# Connections.net
KiCad netlist of a schematic drawn in Altium Designer
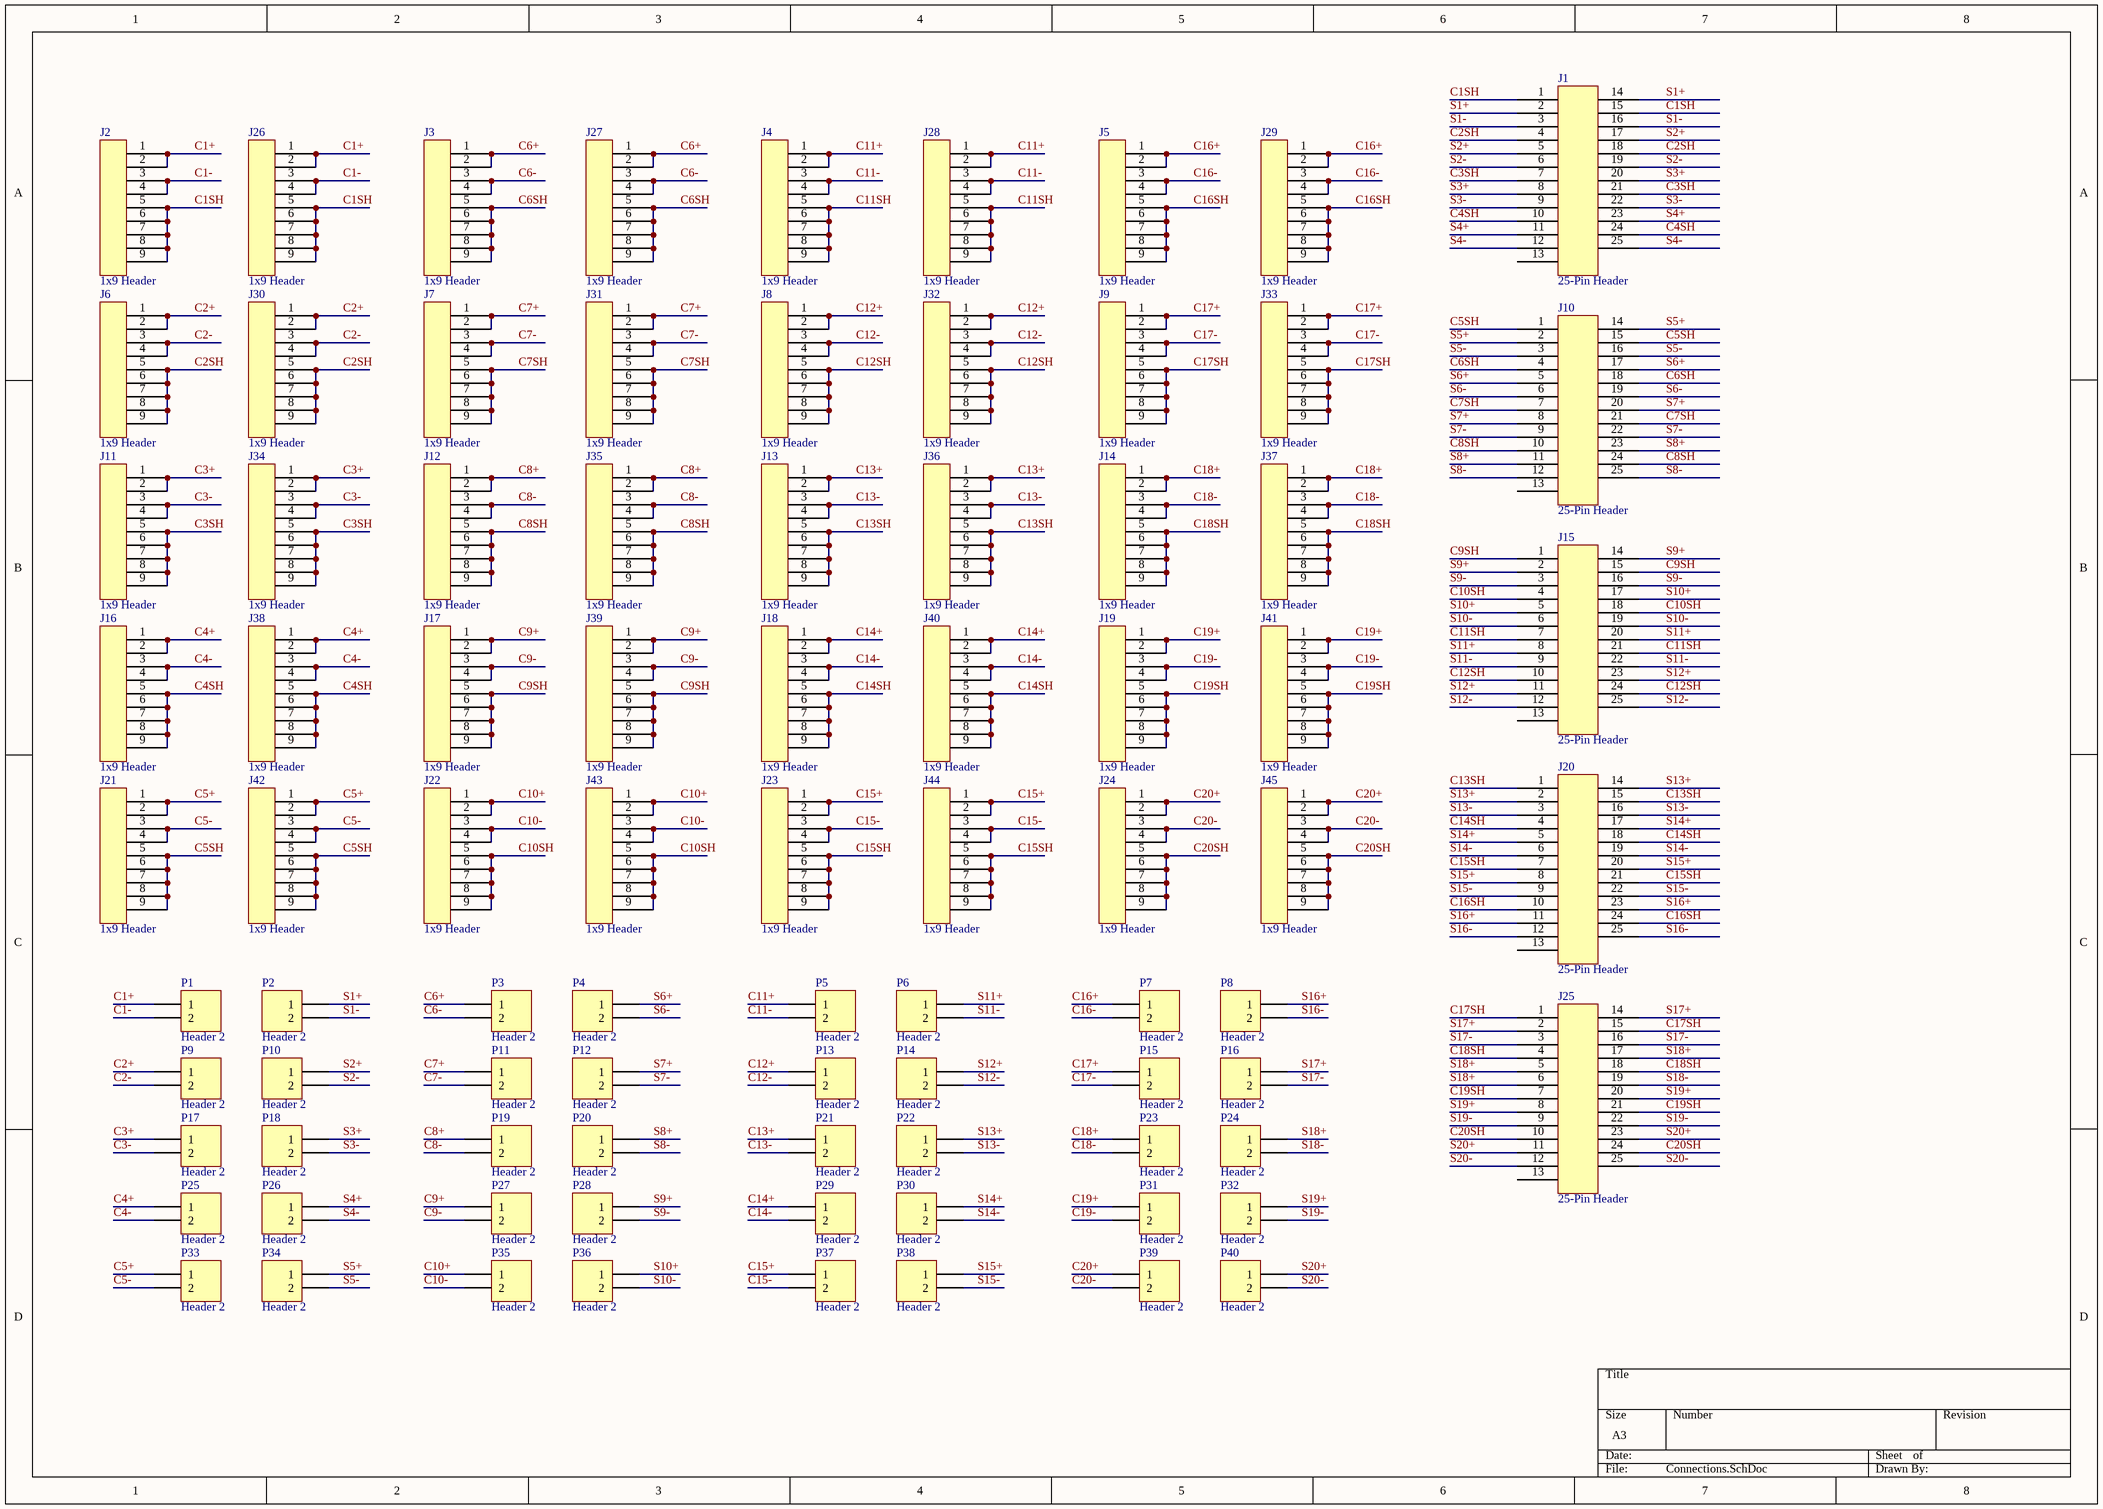
[diagram p0: Connections.SchDoc]

(export (version "E")
  (design (tool "Eeschema 10.0.6"))
  (components
    (comp (ref "J1")
      (value "25-Pin Header")
      (footprint "25-DSub-Rightangle-Female")
      (description "25-Pin Header DSub")
      (libsource (lib "Schematic_Components") (part "25-Pin Header"))
    )
    (comp (ref "J2")
      (value "1x9 Header")
      (footprint "D-SUB-9PIN-TE")
      (libsource (lib "Schematic_Components") (part "1x9 Header"))
    )
    (comp (ref "J3")
      (value "1x9 Header")
      (footprint "D-SUB-9PIN-TE")
      (libsource (lib "Schematic_Components") (part "1x9 Header"))
    )
    (comp (ref "J4")
      (value "1x9 Header")
      (footprint "D-SUB-9PIN-TE")
      (libsource (lib "Schematic_Components") (part "1x9 Header"))
    )
    (comp (ref "J5")
      (value "1x9 Header")
      (footprint "D-SUB-9PIN-TE")
      (libsource (lib "Schematic_Components") (part "1x9 Header"))
    )
    (comp (ref "J6")
      (value "1x9 Header")
      (footprint "D-SUB-9PIN-TE")
      (libsource (lib "Schematic_Components") (part "1x9 Header"))
    )
    (comp (ref "J7")
      (value "1x9 Header")
      (footprint "D-SUB-9PIN-TE")
      (libsource (lib "Schematic_Components") (part "1x9 Header"))
    )
    (comp (ref "J8")
      (value "1x9 Header")
      (footprint "D-SUB-9PIN-TE")
      (libsource (lib "Schematic_Components") (part "1x9 Header"))
    )
    (comp (ref "J9")
      (value "1x9 Header")
      (footprint "D-SUB-9PIN-TE")
      (libsource (lib "Schematic_Components") (part "1x9 Header"))
    )
    (comp (ref "J10")
      (value "25-Pin Header")
      (footprint "25-DSub-Rightangle-Female")
      (description "25-Pin Header DSub")
      (libsource (lib "Schematic_Components") (part "25-Pin Header"))
    )
    (comp (ref "J11")
      (value "1x9 Header")
      (footprint "D-SUB-9PIN-TE")
      (libsource (lib "Schematic_Components") (part "1x9 Header"))
    )
    (comp (ref "J12")
      (value "1x9 Header")
      (footprint "D-SUB-9PIN-TE")
      (libsource (lib "Schematic_Components") (part "1x9 Header"))
    )
    (comp (ref "J13")
      (value "1x9 Header")
      (footprint "D-SUB-9PIN-TE")
      (libsource (lib "Schematic_Components") (part "1x9 Header"))
    )
    (comp (ref "J14")
      (value "1x9 Header")
      (footprint "D-SUB-9PIN-TE")
      (libsource (lib "Schematic_Components") (part "1x9 Header"))
    )
    (comp (ref "J15")
      (value "25-Pin Header")
      (footprint "25-DSub-Rightangle-Female")
      (description "25-Pin Header DSub")
      (libsource (lib "Schematic_Components") (part "25-Pin Header"))
    )
    (comp (ref "J16")
      (value "1x9 Header")
      (footprint "D-SUB-9PIN-TE")
      (libsource (lib "Schematic_Components") (part "1x9 Header"))
    )
    (comp (ref "J17")
      (value "1x9 Header")
      (footprint "D-SUB-9PIN-TE")
      (libsource (lib "Schematic_Components") (part "1x9 Header"))
    )
    (comp (ref "J18")
      (value "1x9 Header")
      (footprint "D-SUB-9PIN-TE")
      (libsource (lib "Schematic_Components") (part "1x9 Header"))
    )
    (comp (ref "J19")
      (value "1x9 Header")
      (footprint "D-SUB-9PIN-TE")
      (libsource (lib "Schematic_Components") (part "1x9 Header"))
    )
    (comp (ref "J20")
      (value "25-Pin Header")
      (footprint "25-DSub-Rightangle-Female")
      (description "25-Pin Header DSub")
      (libsource (lib "Schematic_Components") (part "25-Pin Header"))
    )
    (comp (ref "J21")
      (value "1x9 Header")
      (footprint "D-SUB-9PIN-TE")
      (libsource (lib "Schematic_Components") (part "1x9 Header"))
    )
    (comp (ref "J22")
      (value "1x9 Header")
      (footprint "D-SUB-9PIN-TE")
      (libsource (lib "Schematic_Components") (part "1x9 Header"))
    )
    (comp (ref "J23")
      (value "1x9 Header")
      (footprint "D-SUB-9PIN-TE")
      (libsource (lib "Schematic_Components") (part "1x9 Header"))
    )
    (comp (ref "J24")
      (value "1x9 Header")
      (footprint "D-SUB-9PIN-TE")
      (libsource (lib "Schematic_Components") (part "1x9 Header"))
    )
    (comp (ref "J25")
      (value "25-Pin Header")
      (footprint "25-DSub-Rightangle-Female")
      (description "25-Pin Header DSub")
      (libsource (lib "Schematic_Components") (part "25-Pin Header"))
    )
    (comp (ref "J26")
      (value "1x9 Header")
      (footprint "D-SUB-9PIN-TE")
      (libsource (lib "Schematic_Components") (part "1x9 Header"))
    )
    (comp (ref "J27")
      (value "1x9 Header")
      (footprint "D-SUB-9PIN-TE")
      (libsource (lib "Schematic_Components") (part "1x9 Header"))
    )
    (comp (ref "J28")
      (value "1x9 Header")
      (footprint "D-SUB-9PIN-TE")
      (libsource (lib "Schematic_Components") (part "1x9 Header"))
    )
    (comp (ref "J29")
      (value "1x9 Header")
      (footprint "D-SUB-9PIN-TE")
      (libsource (lib "Schematic_Components") (part "1x9 Header"))
    )
    (comp (ref "J30")
      (value "1x9 Header")
      (footprint "D-SUB-9PIN-TE")
      (libsource (lib "Schematic_Components") (part "1x9 Header"))
    )
    (comp (ref "J31")
      (value "1x9 Header")
      (footprint "D-SUB-9PIN-TE")
      (libsource (lib "Schematic_Components") (part "1x9 Header"))
    )
    (comp (ref "J32")
      (value "1x9 Header")
      (footprint "D-SUB-9PIN-TE")
      (libsource (lib "Schematic_Components") (part "1x9 Header"))
    )
    (comp (ref "J33")
      (value "1x9 Header")
      (footprint "D-SUB-9PIN-TE")
      (libsource (lib "Schematic_Components") (part "1x9 Header"))
    )
    (comp (ref "J34")
      (value "1x9 Header")
      (footprint "D-SUB-9PIN-TE")
      (libsource (lib "Schematic_Components") (part "1x9 Header"))
    )
    (comp (ref "J35")
      (value "1x9 Header")
      (footprint "D-SUB-9PIN-TE")
      (libsource (lib "Schematic_Components") (part "1x9 Header"))
    )
    (comp (ref "J36")
      (value "1x9 Header")
      (footprint "D-SUB-9PIN-TE")
      (libsource (lib "Schematic_Components") (part "1x9 Header"))
    )
    (comp (ref "J37")
      (value "1x9 Header")
      (footprint "D-SUB-9PIN-TE")
      (libsource (lib "Schematic_Components") (part "1x9 Header"))
    )
    (comp (ref "J38")
      (value "1x9 Header")
      (footprint "D-SUB-9PIN-TE")
      (libsource (lib "Schematic_Components") (part "1x9 Header"))
    )
    (comp (ref "J39")
      (value "1x9 Header")
      (footprint "D-SUB-9PIN-TE")
      (libsource (lib "Schematic_Components") (part "1x9 Header"))
    )
    (comp (ref "J40")
      (value "1x9 Header")
      (footprint "D-SUB-9PIN-TE")
      (libsource (lib "Schematic_Components") (part "1x9 Header"))
    )
    (comp (ref "J41")
      (value "1x9 Header")
      (footprint "D-SUB-9PIN-TE")
      (libsource (lib "Schematic_Components") (part "1x9 Header"))
    )
    (comp (ref "J42")
      (value "1x9 Header")
      (footprint "D-SUB-9PIN-TE")
      (libsource (lib "Schematic_Components") (part "1x9 Header"))
    )
    (comp (ref "J43")
      (value "1x9 Header")
      (footprint "D-SUB-9PIN-TE")
      (libsource (lib "Schematic_Components") (part "1x9 Header"))
    )
    (comp (ref "J44")
      (value "1x9 Header")
      (footprint "D-SUB-9PIN-TE")
      (libsource (lib "Schematic_Components") (part "1x9 Header"))
    )
    (comp (ref "J45")
      (value "1x9 Header")
      (footprint "D-SUB-9PIN-TE")
      (libsource (lib "Schematic_Components") (part "1x9 Header"))
    )
    (comp (ref "P1")
      (value "Header 2")
      (footprint "HDR1X2")
      (description "Header, 2-Pin")
      (fields (field (name "PUBLISHER") "Altium Limited"))
      (libsource (lib "Miscellaneous Connectors") (part "Header 2"))
    )
    (comp (ref "P2")
      (value "Header 2")
      (footprint "HDR1X2")
      (description "Header, 2-Pin")
      (fields (field (name "PUBLISHER") "Altium Limited"))
      (libsource (lib "") (part "Header 2_1"))
    )
    (comp (ref "P3")
      (value "Header 2")
      (footprint "HDR1X2")
      (description "Header, 2-Pin")
      (fields (field (name "PUBLISHER") "Altium Limited"))
      (libsource (lib "Miscellaneous Connectors") (part "Header 2"))
    )
    (comp (ref "P4")
      (value "Header 2")
      (footprint "HDR1X2")
      (description "Header, 2-Pin")
      (fields (field (name "PUBLISHER") "Altium Limited"))
      (libsource (lib "") (part "Header 2_1"))
    )
    (comp (ref "P5")
      (value "Header 2")
      (footprint "HDR1X2")
      (description "Header, 2-Pin")
      (fields (field (name "PUBLISHER") "Altium Limited"))
      (libsource (lib "Miscellaneous Connectors") (part "Header 2"))
    )
    (comp (ref "P6")
      (value "Header 2")
      (footprint "HDR1X2")
      (description "Header, 2-Pin")
      (fields (field (name "PUBLISHER") "Altium Limited"))
      (libsource (lib "") (part "Header 2_1"))
    )
    (comp (ref "P7")
      (value "Header 2")
      (footprint "HDR1X2")
      (description "Header, 2-Pin")
      (fields (field (name "PUBLISHER") "Altium Limited"))
      (libsource (lib "Miscellaneous Connectors") (part "Header 2"))
    )
    (comp (ref "P8")
      (value "Header 2")
      (footprint "HDR1X2")
      (description "Header, 2-Pin")
      (fields (field (name "PUBLISHER") "Altium Limited"))
      (libsource (lib "") (part "Header 2_1"))
    )
    (comp (ref "P9")
      (value "Header 2")
      (footprint "HDR1X2")
      (description "Header, 2-Pin")
      (fields (field (name "PUBLISHER") "Altium Limited"))
      (libsource (lib "Miscellaneous Connectors") (part "Header 2"))
    )
    (comp (ref "P10")
      (value "Header 2")
      (footprint "HDR1X2")
      (description "Header, 2-Pin")
      (fields (field (name "PUBLISHER") "Altium Limited"))
      (libsource (lib "") (part "Header 2_1"))
    )
    (comp (ref "P11")
      (value "Header 2")
      (footprint "HDR1X2")
      (description "Header, 2-Pin")
      (fields (field (name "PUBLISHER") "Altium Limited"))
      (libsource (lib "Miscellaneous Connectors") (part "Header 2"))
    )
    (comp (ref "P12")
      (value "Header 2")
      (footprint "HDR1X2")
      (description "Header, 2-Pin")
      (fields (field (name "PUBLISHER") "Altium Limited"))
      (libsource (lib "") (part "Header 2_1"))
    )
    (comp (ref "P13")
      (value "Header 2")
      (footprint "HDR1X2")
      (description "Header, 2-Pin")
      (fields (field (name "PUBLISHER") "Altium Limited"))
      (libsource (lib "Miscellaneous Connectors") (part "Header 2"))
    )
    (comp (ref "P14")
      (value "Header 2")
      (footprint "HDR1X2")
      (description "Header, 2-Pin")
      (fields (field (name "PUBLISHER") "Altium Limited"))
      (libsource (lib "") (part "Header 2_1"))
    )
    (comp (ref "P15")
      (value "Header 2")
      (footprint "HDR1X2")
      (description "Header, 2-Pin")
      (fields (field (name "PUBLISHER") "Altium Limited"))
      (libsource (lib "Miscellaneous Connectors") (part "Header 2"))
    )
    (comp (ref "P16")
      (value "Header 2")
      (footprint "HDR1X2")
      (description "Header, 2-Pin")
      (fields (field (name "PUBLISHER") "Altium Limited"))
      (libsource (lib "") (part "Header 2_1"))
    )
    (comp (ref "P17")
      (value "Header 2")
      (footprint "HDR1X2")
      (description "Header, 2-Pin")
      (fields (field (name "PUBLISHER") "Altium Limited"))
      (libsource (lib "Miscellaneous Connectors") (part "Header 2"))
    )
    (comp (ref "P18")
      (value "Header 2")
      (footprint "HDR1X2")
      (description "Header, 2-Pin")
      (fields (field (name "PUBLISHER") "Altium Limited"))
      (libsource (lib "") (part "Header 2_1"))
    )
    (comp (ref "P19")
      (value "Header 2")
      (footprint "HDR1X2")
      (description "Header, 2-Pin")
      (fields (field (name "PUBLISHER") "Altium Limited"))
      (libsource (lib "Miscellaneous Connectors") (part "Header 2"))
    )
    (comp (ref "P20")
      (value "Header 2")
      (footprint "HDR1X2")
      (description "Header, 2-Pin")
      (fields (field (name "PUBLISHER") "Altium Limited"))
      (libsource (lib "") (part "Header 2_1"))
    )
    (comp (ref "P21")
      (value "Header 2")
      (footprint "HDR1X2")
      (description "Header, 2-Pin")
      (fields (field (name "PUBLISHER") "Altium Limited"))
      (libsource (lib "Miscellaneous Connectors") (part "Header 2"))
    )
    (comp (ref "P22")
      (value "Header 2")
      (footprint "HDR1X2")
      (description "Header, 2-Pin")
      (fields (field (name "PUBLISHER") "Altium Limited"))
      (libsource (lib "") (part "Header 2_1"))
    )
    (comp (ref "P23")
      (value "Header 2")
      (footprint "HDR1X2")
      (description "Header, 2-Pin")
      (fields (field (name "PUBLISHER") "Altium Limited"))
      (libsource (lib "Miscellaneous Connectors") (part "Header 2"))
    )
    (comp (ref "P24")
      (value "Header 2")
      (footprint "HDR1X2")
      (description "Header, 2-Pin")
      (fields (field (name "PUBLISHER") "Altium Limited"))
      (libsource (lib "") (part "Header 2_1"))
    )
    (comp (ref "P25")
      (value "Header 2")
      (footprint "HDR1X2")
      (description "Header, 2-Pin")
      (fields (field (name "PUBLISHER") "Altium Limited"))
      (libsource (lib "Miscellaneous Connectors") (part "Header 2"))
    )
    (comp (ref "P26")
      (value "Header 2")
      (footprint "HDR1X2")
      (description "Header, 2-Pin")
      (fields (field (name "PUBLISHER") "Altium Limited"))
      (libsource (lib "") (part "Header 2_1"))
    )
    (comp (ref "P27")
      (value "Header 2")
      (footprint "HDR1X2")
      (description "Header, 2-Pin")
      (fields (field (name "PUBLISHER") "Altium Limited"))
      (libsource (lib "Miscellaneous Connectors") (part "Header 2"))
    )
    (comp (ref "P28")
      (value "Header 2")
      (footprint "HDR1X2")
      (description "Header, 2-Pin")
      (fields (field (name "PUBLISHER") "Altium Limited"))
      (libsource (lib "") (part "Header 2_1"))
    )
    (comp (ref "P29")
      (value "Header 2")
      (footprint "HDR1X2")
      (description "Header, 2-Pin")
      (fields (field (name "PUBLISHER") "Altium Limited"))
      (libsource (lib "Miscellaneous Connectors") (part "Header 2"))
    )
    (comp (ref "P30")
      (value "Header 2")
      (footprint "HDR1X2")
      (description "Header, 2-Pin")
      (fields (field (name "PUBLISHER") "Altium Limited"))
      (libsource (lib "") (part "Header 2_1"))
    )
    (comp (ref "P31")
      (value "Header 2")
      (footprint "HDR1X2")
      (description "Header, 2-Pin")
      (fields (field (name "PUBLISHER") "Altium Limited"))
      (libsource (lib "Miscellaneous Connectors") (part "Header 2"))
    )
    (comp (ref "P32")
      (value "Header 2")
      (footprint "HDR1X2")
      (description "Header, 2-Pin")
      (fields (field (name "PUBLISHER") "Altium Limited"))
      (libsource (lib "") (part "Header 2_1"))
    )
    (comp (ref "P33")
      (value "Header 2")
      (footprint "HDR1X2")
      (description "Header, 2-Pin")
      (fields (field (name "PUBLISHER") "Altium Limited"))
      (libsource (lib "Miscellaneous Connectors") (part "Header 2"))
    )
    (comp (ref "P34")
      (value "Header 2")
      (footprint "HDR1X2")
      (description "Header, 2-Pin")
      (fields (field (name "PUBLISHER") "Altium Limited"))
      (libsource (lib "") (part "Header 2_1"))
    )
    (comp (ref "P35")
      (value "Header 2")
      (footprint "HDR1X2")
      (description "Header, 2-Pin")
      (fields (field (name "PUBLISHER") "Altium Limited"))
      (libsource (lib "Miscellaneous Connectors") (part "Header 2"))
    )
    (comp (ref "P36")
      (value "Header 2")
      (footprint "HDR1X2")
      (description "Header, 2-Pin")
      (fields (field (name "PUBLISHER") "Altium Limited"))
      (libsource (lib "") (part "Header 2_1"))
    )
    (comp (ref "P37")
      (value "Header 2")
      (footprint "HDR1X2")
      (description "Header, 2-Pin")
      (fields (field (name "PUBLISHER") "Altium Limited"))
      (libsource (lib "Miscellaneous Connectors") (part "Header 2"))
    )
    (comp (ref "P38")
      (value "Header 2")
      (footprint "HDR1X2")
      (description "Header, 2-Pin")
      (fields (field (name "PUBLISHER") "Altium Limited"))
      (libsource (lib "") (part "Header 2_1"))
    )
    (comp (ref "P39")
      (value "Header 2")
      (footprint "HDR1X2")
      (description "Header, 2-Pin")
      (fields (field (name "PUBLISHER") "Altium Limited"))
      (libsource (lib "Miscellaneous Connectors") (part "Header 2"))
    )
    (comp (ref "P40")
      (value "Header 2")
      (footprint "HDR1X2")
      (description "Header, 2-Pin")
      (fields (field (name "PUBLISHER") "Altium Limited"))
      (libsource (lib "") (part "Header 2_1"))
    )
  )
  (nets
    (net (code "1") (name "/C1+") (class "Default")
      (node (ref "J2") (pin "1") (pintype "passive"))
      (node (ref "J2") (pin "2") (pintype "passive"))
      (node (ref "J26") (pin "1") (pintype "passive"))
      (node (ref "J26") (pin "2") (pintype "passive"))
      (node (ref "P1") (pin "1") (pinfunction "1_1") (pintype "passive"))
    )
    (net (code "2") (name "/C1-") (class "Default")
      (node (ref "J2") (pin "3") (pintype "passive"))
      (node (ref "J2") (pin "4") (pintype "passive"))
      (node (ref "J26") (pin "3") (pintype "passive"))
      (node (ref "J26") (pin "4") (pintype "passive"))
      (node (ref "P1") (pin "2") (pinfunction "2_2") (pintype "passive"))
    )
    (net (code "3") (name "/C1SH") (class "Default")
      (node (ref "J1") (pin "1") (pintype "passive"))
      (node (ref "J1") (pin "15") (pintype "passive"))
      (node (ref "J2") (pin "5") (pintype "passive"))
      (node (ref "J2") (pin "6") (pintype "passive"))
      (node (ref "J2") (pin "7") (pintype "passive"))
      (node (ref "J2") (pin "8") (pintype "passive"))
      (node (ref "J2") (pin "9") (pintype "passive"))
      (node (ref "J26") (pin "5") (pintype "passive"))
      (node (ref "J26") (pin "6") (pintype "passive"))
      (node (ref "J26") (pin "7") (pintype "passive"))
      (node (ref "J26") (pin "8") (pintype "passive"))
      (node (ref "J26") (pin "9") (pintype "passive"))
    )
    (net (code "4") (name "/C2+") (class "Default")
      (node (ref "J30") (pin "1") (pintype "passive"))
      (node (ref "J30") (pin "2") (pintype "passive"))
      (node (ref "J6") (pin "1") (pintype "passive"))
      (node (ref "J6") (pin "2") (pintype "passive"))
      (node (ref "P9") (pin "1") (pinfunction "1_1") (pintype "passive"))
    )
    (net (code "5") (name "/C2-") (class "Default")
      (node (ref "J30") (pin "3") (pintype "passive"))
      (node (ref "J30") (pin "4") (pintype "passive"))
      (node (ref "J6") (pin "3") (pintype "passive"))
      (node (ref "J6") (pin "4") (pintype "passive"))
      (node (ref "P9") (pin "2") (pinfunction "2_2") (pintype "passive"))
    )
    (net (code "6") (name "/C2SH") (class "Default")
      (node (ref "J1") (pin "18") (pintype "passive"))
      (node (ref "J1") (pin "4") (pintype "passive"))
      (node (ref "J30") (pin "5") (pintype "passive"))
      (node (ref "J30") (pin "6") (pintype "passive"))
      (node (ref "J30") (pin "7") (pintype "passive"))
      (node (ref "J30") (pin "8") (pintype "passive"))
      (node (ref "J30") (pin "9") (pintype "passive"))
      (node (ref "J6") (pin "5") (pintype "passive"))
      (node (ref "J6") (pin "6") (pintype "passive"))
      (node (ref "J6") (pin "7") (pintype "passive"))
      (node (ref "J6") (pin "8") (pintype "passive"))
      (node (ref "J6") (pin "9") (pintype "passive"))
    )
    (net (code "7") (name "/C3+") (class "Default")
      (node (ref "J11") (pin "1") (pintype "passive"))
      (node (ref "J11") (pin "2") (pintype "passive"))
      (node (ref "J34") (pin "1") (pintype "passive"))
      (node (ref "J34") (pin "2") (pintype "passive"))
      (node (ref "P17") (pin "1") (pinfunction "1_1") (pintype "passive"))
    )
    (net (code "8") (name "/C3-") (class "Default")
      (node (ref "J11") (pin "3") (pintype "passive"))
      (node (ref "J11") (pin "4") (pintype "passive"))
      (node (ref "J34") (pin "3") (pintype "passive"))
      (node (ref "J34") (pin "4") (pintype "passive"))
      (node (ref "P17") (pin "2") (pinfunction "2_2") (pintype "passive"))
    )
    (net (code "9") (name "/C3SH") (class "Default")
      (node (ref "J1") (pin "21") (pintype "passive"))
      (node (ref "J1") (pin "7") (pintype "passive"))
      (node (ref "J11") (pin "5") (pintype "passive"))
      (node (ref "J11") (pin "6") (pintype "passive"))
      (node (ref "J11") (pin "7") (pintype "passive"))
      (node (ref "J11") (pin "8") (pintype "passive"))
      (node (ref "J11") (pin "9") (pintype "passive"))
      (node (ref "J34") (pin "5") (pintype "passive"))
      (node (ref "J34") (pin "6") (pintype "passive"))
      (node (ref "J34") (pin "7") (pintype "passive"))
      (node (ref "J34") (pin "8") (pintype "passive"))
      (node (ref "J34") (pin "9") (pintype "passive"))
    )
    (net (code "10") (name "/C4+") (class "Default")
      (node (ref "J16") (pin "1") (pintype "passive"))
      (node (ref "J16") (pin "2") (pintype "passive"))
      (node (ref "J38") (pin "1") (pintype "passive"))
      (node (ref "J38") (pin "2") (pintype "passive"))
      (node (ref "P25") (pin "1") (pinfunction "1_1") (pintype "passive"))
    )
    (net (code "11") (name "/C4-") (class "Default")
      (node (ref "J16") (pin "3") (pintype "passive"))
      (node (ref "J16") (pin "4") (pintype "passive"))
      (node (ref "J38") (pin "3") (pintype "passive"))
      (node (ref "J38") (pin "4") (pintype "passive"))
      (node (ref "P25") (pin "2") (pinfunction "2_2") (pintype "passive"))
    )
    (net (code "12") (name "/C4SH") (class "Default")
      (node (ref "J1") (pin "10") (pintype "passive"))
      (node (ref "J1") (pin "24") (pintype "passive"))
      (node (ref "J16") (pin "5") (pintype "passive"))
      (node (ref "J16") (pin "6") (pintype "passive"))
      (node (ref "J16") (pin "7") (pintype "passive"))
      (node (ref "J16") (pin "8") (pintype "passive"))
      (node (ref "J16") (pin "9") (pintype "passive"))
      (node (ref "J38") (pin "5") (pintype "passive"))
      (node (ref "J38") (pin "6") (pintype "passive"))
      (node (ref "J38") (pin "7") (pintype "passive"))
      (node (ref "J38") (pin "8") (pintype "passive"))
      (node (ref "J38") (pin "9") (pintype "passive"))
    )
    (net (code "13") (name "/C5+") (class "Default")
      (node (ref "J21") (pin "1") (pintype "passive"))
      (node (ref "J21") (pin "2") (pintype "passive"))
      (node (ref "J42") (pin "1") (pintype "passive"))
      (node (ref "J42") (pin "2") (pintype "passive"))
      (node (ref "P33") (pin "1") (pinfunction "1_1") (pintype "passive"))
    )
    (net (code "14") (name "/C5-") (class "Default")
      (node (ref "J21") (pin "3") (pintype "passive"))
      (node (ref "J21") (pin "4") (pintype "passive"))
      (node (ref "J42") (pin "3") (pintype "passive"))
      (node (ref "J42") (pin "4") (pintype "passive"))
      (node (ref "P33") (pin "2") (pinfunction "2_2") (pintype "passive"))
    )
    (net (code "15") (name "/C5SH") (class "Default")
      (node (ref "J10") (pin "1") (pintype "passive"))
      (node (ref "J10") (pin "15") (pintype "passive"))
      (node (ref "J21") (pin "5") (pintype "passive"))
      (node (ref "J21") (pin "6") (pintype "passive"))
      (node (ref "J21") (pin "7") (pintype "passive"))
      (node (ref "J21") (pin "8") (pintype "passive"))
      (node (ref "J21") (pin "9") (pintype "passive"))
      (node (ref "J42") (pin "5") (pintype "passive"))
      (node (ref "J42") (pin "6") (pintype "passive"))
      (node (ref "J42") (pin "7") (pintype "passive"))
      (node (ref "J42") (pin "8") (pintype "passive"))
      (node (ref "J42") (pin "9") (pintype "passive"))
    )
    (net (code "16") (name "/C6+") (class "Default")
      (node (ref "J27") (pin "1") (pintype "passive"))
      (node (ref "J27") (pin "2") (pintype "passive"))
      (node (ref "J3") (pin "1") (pintype "passive"))
      (node (ref "J3") (pin "2") (pintype "passive"))
      (node (ref "P3") (pin "1") (pinfunction "1_1") (pintype "passive"))
    )
    (net (code "17") (name "/C6-") (class "Default")
      (node (ref "J27") (pin "3") (pintype "passive"))
      (node (ref "J27") (pin "4") (pintype "passive"))
      (node (ref "J3") (pin "3") (pintype "passive"))
      (node (ref "J3") (pin "4") (pintype "passive"))
      (node (ref "P3") (pin "2") (pinfunction "2_2") (pintype "passive"))
    )
    (net (code "18") (name "/C6SH") (class "Default")
      (node (ref "J10") (pin "18") (pintype "passive"))
      (node (ref "J10") (pin "4") (pintype "passive"))
      (node (ref "J27") (pin "5") (pintype "passive"))
      (node (ref "J27") (pin "6") (pintype "passive"))
      (node (ref "J27") (pin "7") (pintype "passive"))
      (node (ref "J27") (pin "8") (pintype "passive"))
      (node (ref "J27") (pin "9") (pintype "passive"))
      (node (ref "J3") (pin "5") (pintype "passive"))
      (node (ref "J3") (pin "6") (pintype "passive"))
      (node (ref "J3") (pin "7") (pintype "passive"))
      (node (ref "J3") (pin "8") (pintype "passive"))
      (node (ref "J3") (pin "9") (pintype "passive"))
    )
    (net (code "19") (name "/C7+") (class "Default")
      (node (ref "J31") (pin "1") (pintype "passive"))
      (node (ref "J31") (pin "2") (pintype "passive"))
      (node (ref "J7") (pin "1") (pintype "passive"))
      (node (ref "J7") (pin "2") (pintype "passive"))
      (node (ref "P11") (pin "1") (pinfunction "1_1") (pintype "passive"))
    )
    (net (code "20") (name "/C7-") (class "Default")
      (node (ref "J31") (pin "3") (pintype "passive"))
      (node (ref "J31") (pin "4") (pintype "passive"))
      (node (ref "J7") (pin "3") (pintype "passive"))
      (node (ref "J7") (pin "4") (pintype "passive"))
      (node (ref "P11") (pin "2") (pinfunction "2_2") (pintype "passive"))
    )
    (net (code "21") (name "/C7SH") (class "Default")
      (node (ref "J10") (pin "21") (pintype "passive"))
      (node (ref "J10") (pin "7") (pintype "passive"))
      (node (ref "J31") (pin "5") (pintype "passive"))
      (node (ref "J31") (pin "6") (pintype "passive"))
      (node (ref "J31") (pin "7") (pintype "passive"))
      (node (ref "J31") (pin "8") (pintype "passive"))
      (node (ref "J31") (pin "9") (pintype "passive"))
      (node (ref "J7") (pin "5") (pintype "passive"))
      (node (ref "J7") (pin "6") (pintype "passive"))
      (node (ref "J7") (pin "7") (pintype "passive"))
      (node (ref "J7") (pin "8") (pintype "passive"))
      (node (ref "J7") (pin "9") (pintype "passive"))
    )
    (net (code "22") (name "/C8+") (class "Default")
      (node (ref "J12") (pin "1") (pintype "passive"))
      (node (ref "J12") (pin "2") (pintype "passive"))
      (node (ref "J35") (pin "1") (pintype "passive"))
      (node (ref "J35") (pin "2") (pintype "passive"))
      (node (ref "P19") (pin "1") (pinfunction "1_1") (pintype "passive"))
    )
    (net (code "23") (name "/C8-") (class "Default")
      (node (ref "J12") (pin "3") (pintype "passive"))
      (node (ref "J12") (pin "4") (pintype "passive"))
      (node (ref "J35") (pin "3") (pintype "passive"))
      (node (ref "J35") (pin "4") (pintype "passive"))
      (node (ref "P19") (pin "2") (pinfunction "2_2") (pintype "passive"))
    )
    (net (code "24") (name "/C8SH") (class "Default")
      (node (ref "J10") (pin "10") (pintype "passive"))
      (node (ref "J10") (pin "24") (pintype "passive"))
      (node (ref "J12") (pin "5") (pintype "passive"))
      (node (ref "J12") (pin "6") (pintype "passive"))
      (node (ref "J12") (pin "7") (pintype "passive"))
      (node (ref "J12") (pin "8") (pintype "passive"))
      (node (ref "J12") (pin "9") (pintype "passive"))
      (node (ref "J35") (pin "5") (pintype "passive"))
      (node (ref "J35") (pin "6") (pintype "passive"))
      (node (ref "J35") (pin "7") (pintype "passive"))
      (node (ref "J35") (pin "8") (pintype "passive"))
      (node (ref "J35") (pin "9") (pintype "passive"))
    )
    (net (code "25") (name "/C9+") (class "Default")
      (node (ref "J17") (pin "1") (pintype "passive"))
      (node (ref "J17") (pin "2") (pintype "passive"))
      (node (ref "J39") (pin "1") (pintype "passive"))
      (node (ref "J39") (pin "2") (pintype "passive"))
      (node (ref "P27") (pin "1") (pinfunction "1_1") (pintype "passive"))
    )
    (net (code "26") (name "/C9-") (class "Default")
      (node (ref "J17") (pin "3") (pintype "passive"))
      (node (ref "J17") (pin "4") (pintype "passive"))
      (node (ref "J39") (pin "3") (pintype "passive"))
      (node (ref "J39") (pin "4") (pintype "passive"))
      (node (ref "P27") (pin "2") (pinfunction "2_2") (pintype "passive"))
    )
    (net (code "27") (name "/C9SH") (class "Default")
      (node (ref "J15") (pin "1") (pintype "passive"))
      (node (ref "J15") (pin "15") (pintype "passive"))
      (node (ref "J17") (pin "5") (pintype "passive"))
      (node (ref "J17") (pin "6") (pintype "passive"))
      (node (ref "J17") (pin "7") (pintype "passive"))
      (node (ref "J17") (pin "8") (pintype "passive"))
      (node (ref "J17") (pin "9") (pintype "passive"))
      (node (ref "J39") (pin "5") (pintype "passive"))
      (node (ref "J39") (pin "6") (pintype "passive"))
      (node (ref "J39") (pin "7") (pintype "passive"))
      (node (ref "J39") (pin "8") (pintype "passive"))
      (node (ref "J39") (pin "9") (pintype "passive"))
    )
    (net (code "28") (name "/C10+") (class "Default")
      (node (ref "J22") (pin "1") (pintype "passive"))
      (node (ref "J22") (pin "2") (pintype "passive"))
      (node (ref "J43") (pin "1") (pintype "passive"))
      (node (ref "J43") (pin "2") (pintype "passive"))
      (node (ref "P35") (pin "1") (pinfunction "1_1") (pintype "passive"))
    )
    (net (code "29") (name "/C10-") (class "Default")
      (node (ref "J22") (pin "3") (pintype "passive"))
      (node (ref "J22") (pin "4") (pintype "passive"))
      (node (ref "J43") (pin "3") (pintype "passive"))
      (node (ref "J43") (pin "4") (pintype "passive"))
      (node (ref "P35") (pin "2") (pinfunction "2_2") (pintype "passive"))
    )
    (net (code "30") (name "/C10SH") (class "Default")
      (node (ref "J15") (pin "18") (pintype "passive"))
      (node (ref "J15") (pin "4") (pintype "passive"))
      (node (ref "J22") (pin "5") (pintype "passive"))
      (node (ref "J22") (pin "6") (pintype "passive"))
      (node (ref "J22") (pin "7") (pintype "passive"))
      (node (ref "J22") (pin "8") (pintype "passive"))
      (node (ref "J22") (pin "9") (pintype "passive"))
      (node (ref "J43") (pin "5") (pintype "passive"))
      (node (ref "J43") (pin "6") (pintype "passive"))
      (node (ref "J43") (pin "7") (pintype "passive"))
      (node (ref "J43") (pin "8") (pintype "passive"))
      (node (ref "J43") (pin "9") (pintype "passive"))
    )
    (net (code "31") (name "/C11+") (class "Default")
      (node (ref "J28") (pin "1") (pintype "passive"))
      (node (ref "J28") (pin "2") (pintype "passive"))
      (node (ref "J4") (pin "1") (pintype "passive"))
      (node (ref "J4") (pin "2") (pintype "passive"))
      (node (ref "P5") (pin "1") (pinfunction "1_1") (pintype "passive"))
    )
    (net (code "32") (name "/C11-") (class "Default")
      (node (ref "J28") (pin "3") (pintype "passive"))
      (node (ref "J28") (pin "4") (pintype "passive"))
      (node (ref "J4") (pin "3") (pintype "passive"))
      (node (ref "J4") (pin "4") (pintype "passive"))
      (node (ref "P5") (pin "2") (pinfunction "2_2") (pintype "passive"))
    )
    (net (code "33") (name "/C11SH") (class "Default")
      (node (ref "J15") (pin "21") (pintype "passive"))
      (node (ref "J15") (pin "7") (pintype "passive"))
      (node (ref "J28") (pin "5") (pintype "passive"))
      (node (ref "J28") (pin "6") (pintype "passive"))
      (node (ref "J28") (pin "7") (pintype "passive"))
      (node (ref "J28") (pin "8") (pintype "passive"))
      (node (ref "J28") (pin "9") (pintype "passive"))
      (node (ref "J4") (pin "5") (pintype "passive"))
      (node (ref "J4") (pin "6") (pintype "passive"))
      (node (ref "J4") (pin "7") (pintype "passive"))
      (node (ref "J4") (pin "8") (pintype "passive"))
      (node (ref "J4") (pin "9") (pintype "passive"))
    )
    (net (code "34") (name "/C12+") (class "Default")
      (node (ref "J32") (pin "1") (pintype "passive"))
      (node (ref "J32") (pin "2") (pintype "passive"))
      (node (ref "J8") (pin "1") (pintype "passive"))
      (node (ref "J8") (pin "2") (pintype "passive"))
      (node (ref "P13") (pin "1") (pinfunction "1_1") (pintype "passive"))
    )
    (net (code "35") (name "/C12-") (class "Default")
      (node (ref "J32") (pin "3") (pintype "passive"))
      (node (ref "J32") (pin "4") (pintype "passive"))
      (node (ref "J8") (pin "3") (pintype "passive"))
      (node (ref "J8") (pin "4") (pintype "passive"))
      (node (ref "P13") (pin "2") (pinfunction "2_2") (pintype "passive"))
    )
    (net (code "36") (name "/C12SH") (class "Default")
      (node (ref "J15") (pin "10") (pintype "passive"))
      (node (ref "J15") (pin "24") (pintype "passive"))
      (node (ref "J32") (pin "5") (pintype "passive"))
      (node (ref "J32") (pin "6") (pintype "passive"))
      (node (ref "J32") (pin "7") (pintype "passive"))
      (node (ref "J32") (pin "8") (pintype "passive"))
      (node (ref "J32") (pin "9") (pintype "passive"))
      (node (ref "J8") (pin "5") (pintype "passive"))
      (node (ref "J8") (pin "6") (pintype "passive"))
      (node (ref "J8") (pin "7") (pintype "passive"))
      (node (ref "J8") (pin "8") (pintype "passive"))
      (node (ref "J8") (pin "9") (pintype "passive"))
    )
    (net (code "37") (name "/C13+") (class "Default")
      (node (ref "J13") (pin "1") (pintype "passive"))
      (node (ref "J13") (pin "2") (pintype "passive"))
      (node (ref "J36") (pin "1") (pintype "passive"))
      (node (ref "J36") (pin "2") (pintype "passive"))
      (node (ref "P21") (pin "1") (pinfunction "1_1") (pintype "passive"))
    )
    (net (code "38") (name "/C13-") (class "Default")
      (node (ref "J13") (pin "3") (pintype "passive"))
      (node (ref "J13") (pin "4") (pintype "passive"))
      (node (ref "J36") (pin "3") (pintype "passive"))
      (node (ref "J36") (pin "4") (pintype "passive"))
      (node (ref "P21") (pin "2") (pinfunction "2_2") (pintype "passive"))
    )
    (net (code "39") (name "/C13SH") (class "Default")
      (node (ref "J13") (pin "5") (pintype "passive"))
      (node (ref "J13") (pin "6") (pintype "passive"))
      (node (ref "J13") (pin "7") (pintype "passive"))
      (node (ref "J13") (pin "8") (pintype "passive"))
      (node (ref "J13") (pin "9") (pintype "passive"))
      (node (ref "J20") (pin "1") (pintype "passive"))
      (node (ref "J20") (pin "15") (pintype "passive"))
      (node (ref "J36") (pin "5") (pintype "passive"))
      (node (ref "J36") (pin "6") (pintype "passive"))
      (node (ref "J36") (pin "7") (pintype "passive"))
      (node (ref "J36") (pin "8") (pintype "passive"))
      (node (ref "J36") (pin "9") (pintype "passive"))
    )
    (net (code "40") (name "/C14+") (class "Default")
      (node (ref "J18") (pin "1") (pintype "passive"))
      (node (ref "J18") (pin "2") (pintype "passive"))
      (node (ref "J40") (pin "1") (pintype "passive"))
      (node (ref "J40") (pin "2") (pintype "passive"))
      (node (ref "P29") (pin "1") (pinfunction "1_1") (pintype "passive"))
    )
    (net (code "41") (name "/C14-") (class "Default")
      (node (ref "J18") (pin "3") (pintype "passive"))
      (node (ref "J18") (pin "4") (pintype "passive"))
      (node (ref "J40") (pin "3") (pintype "passive"))
      (node (ref "J40") (pin "4") (pintype "passive"))
      (node (ref "P29") (pin "2") (pinfunction "2_2") (pintype "passive"))
    )
    (net (code "42") (name "/C14SH") (class "Default")
      (node (ref "J18") (pin "5") (pintype "passive"))
      (node (ref "J18") (pin "6") (pintype "passive"))
      (node (ref "J18") (pin "7") (pintype "passive"))
      (node (ref "J18") (pin "8") (pintype "passive"))
      (node (ref "J18") (pin "9") (pintype "passive"))
      (node (ref "J20") (pin "18") (pintype "passive"))
      (node (ref "J20") (pin "4") (pintype "passive"))
      (node (ref "J40") (pin "5") (pintype "passive"))
      (node (ref "J40") (pin "6") (pintype "passive"))
      (node (ref "J40") (pin "7") (pintype "passive"))
      (node (ref "J40") (pin "8") (pintype "passive"))
      (node (ref "J40") (pin "9") (pintype "passive"))
    )
    (net (code "43") (name "/C15+") (class "Default")
      (node (ref "J23") (pin "1") (pintype "passive"))
      (node (ref "J23") (pin "2") (pintype "passive"))
      (node (ref "J44") (pin "1") (pintype "passive"))
      (node (ref "J44") (pin "2") (pintype "passive"))
      (node (ref "P37") (pin "1") (pinfunction "1_1") (pintype "passive"))
    )
    (net (code "44") (name "/C15-") (class "Default")
      (node (ref "J23") (pin "3") (pintype "passive"))
      (node (ref "J23") (pin "4") (pintype "passive"))
      (node (ref "J44") (pin "3") (pintype "passive"))
      (node (ref "J44") (pin "4") (pintype "passive"))
      (node (ref "P37") (pin "2") (pinfunction "2_2") (pintype "passive"))
    )
    (net (code "45") (name "/C15SH") (class "Default")
      (node (ref "J20") (pin "21") (pintype "passive"))
      (node (ref "J20") (pin "7") (pintype "passive"))
      (node (ref "J23") (pin "5") (pintype "passive"))
      (node (ref "J23") (pin "6") (pintype "passive"))
      (node (ref "J23") (pin "7") (pintype "passive"))
      (node (ref "J23") (pin "8") (pintype "passive"))
      (node (ref "J23") (pin "9") (pintype "passive"))
      (node (ref "J44") (pin "5") (pintype "passive"))
      (node (ref "J44") (pin "6") (pintype "passive"))
      (node (ref "J44") (pin "7") (pintype "passive"))
      (node (ref "J44") (pin "8") (pintype "passive"))
      (node (ref "J44") (pin "9") (pintype "passive"))
    )
    (net (code "46") (name "/C16+") (class "Default")
      (node (ref "J29") (pin "1") (pintype "passive"))
      (node (ref "J29") (pin "2") (pintype "passive"))
      (node (ref "J5") (pin "1") (pintype "passive"))
      (node (ref "J5") (pin "2") (pintype "passive"))
      (node (ref "P7") (pin "1") (pinfunction "1_1") (pintype "passive"))
    )
    (net (code "47") (name "/C16-") (class "Default")
      (node (ref "J29") (pin "3") (pintype "passive"))
      (node (ref "J29") (pin "4") (pintype "passive"))
      (node (ref "J5") (pin "3") (pintype "passive"))
      (node (ref "J5") (pin "4") (pintype "passive"))
      (node (ref "P7") (pin "2") (pinfunction "2_2") (pintype "passive"))
    )
    (net (code "48") (name "/C16SH") (class "Default")
      (node (ref "J20") (pin "10") (pintype "passive"))
      (node (ref "J20") (pin "24") (pintype "passive"))
      (node (ref "J29") (pin "5") (pintype "passive"))
      (node (ref "J29") (pin "6") (pintype "passive"))
      (node (ref "J29") (pin "7") (pintype "passive"))
      (node (ref "J29") (pin "8") (pintype "passive"))
      (node (ref "J29") (pin "9") (pintype "passive"))
      (node (ref "J5") (pin "5") (pintype "passive"))
      (node (ref "J5") (pin "6") (pintype "passive"))
      (node (ref "J5") (pin "7") (pintype "passive"))
      (node (ref "J5") (pin "8") (pintype "passive"))
      (node (ref "J5") (pin "9") (pintype "passive"))
    )
    (net (code "49") (name "/C17+") (class "Default")
      (node (ref "J33") (pin "1") (pintype "passive"))
      (node (ref "J33") (pin "2") (pintype "passive"))
      (node (ref "J9") (pin "1") (pintype "passive"))
      (node (ref "J9") (pin "2") (pintype "passive"))
      (node (ref "P15") (pin "1") (pinfunction "1_1") (pintype "passive"))
    )
    (net (code "50") (name "/C17-") (class "Default")
      (node (ref "J33") (pin "3") (pintype "passive"))
      (node (ref "J33") (pin "4") (pintype "passive"))
      (node (ref "J9") (pin "3") (pintype "passive"))
      (node (ref "J9") (pin "4") (pintype "passive"))
      (node (ref "P15") (pin "2") (pinfunction "2_2") (pintype "passive"))
    )
    (net (code "51") (name "/C17SH") (class "Default")
      (node (ref "J25") (pin "1") (pintype "passive"))
      (node (ref "J25") (pin "15") (pintype "passive"))
      (node (ref "J33") (pin "5") (pintype "passive"))
      (node (ref "J33") (pin "6") (pintype "passive"))
      (node (ref "J33") (pin "7") (pintype "passive"))
      (node (ref "J33") (pin "8") (pintype "passive"))
      (node (ref "J33") (pin "9") (pintype "passive"))
      (node (ref "J9") (pin "5") (pintype "passive"))
      (node (ref "J9") (pin "6") (pintype "passive"))
      (node (ref "J9") (pin "7") (pintype "passive"))
      (node (ref "J9") (pin "8") (pintype "passive"))
      (node (ref "J9") (pin "9") (pintype "passive"))
    )
    (net (code "52") (name "/C18+") (class "Default")
      (node (ref "J14") (pin "1") (pintype "passive"))
      (node (ref "J14") (pin "2") (pintype "passive"))
      (node (ref "J37") (pin "1") (pintype "passive"))
      (node (ref "J37") (pin "2") (pintype "passive"))
      (node (ref "P23") (pin "1") (pinfunction "1_1") (pintype "passive"))
    )
    (net (code "53") (name "/C18-") (class "Default")
      (node (ref "J14") (pin "3") (pintype "passive"))
      (node (ref "J14") (pin "4") (pintype "passive"))
      (node (ref "J37") (pin "3") (pintype "passive"))
      (node (ref "J37") (pin "4") (pintype "passive"))
      (node (ref "P23") (pin "2") (pinfunction "2_2") (pintype "passive"))
    )
    (net (code "54") (name "/C18SH") (class "Default")
      (node (ref "J14") (pin "5") (pintype "passive"))
      (node (ref "J14") (pin "6") (pintype "passive"))
      (node (ref "J14") (pin "7") (pintype "passive"))
      (node (ref "J14") (pin "8") (pintype "passive"))
      (node (ref "J14") (pin "9") (pintype "passive"))
      (node (ref "J25") (pin "18") (pintype "passive"))
      (node (ref "J25") (pin "4") (pintype "passive"))
      (node (ref "J37") (pin "5") (pintype "passive"))
      (node (ref "J37") (pin "6") (pintype "passive"))
      (node (ref "J37") (pin "7") (pintype "passive"))
      (node (ref "J37") (pin "8") (pintype "passive"))
      (node (ref "J37") (pin "9") (pintype "passive"))
    )
    (net (code "55") (name "/C19+") (class "Default")
      (node (ref "J19") (pin "1") (pintype "passive"))
      (node (ref "J19") (pin "2") (pintype "passive"))
      (node (ref "J41") (pin "1") (pintype "passive"))
      (node (ref "J41") (pin "2") (pintype "passive"))
      (node (ref "P31") (pin "1") (pinfunction "1_1") (pintype "passive"))
    )
    (net (code "56") (name "/C19-") (class "Default")
      (node (ref "J19") (pin "3") (pintype "passive"))
      (node (ref "J19") (pin "4") (pintype "passive"))
      (node (ref "J41") (pin "3") (pintype "passive"))
      (node (ref "J41") (pin "4") (pintype "passive"))
      (node (ref "P31") (pin "2") (pinfunction "2_2") (pintype "passive"))
    )
    (net (code "57") (name "/C19SH") (class "Default")
      (node (ref "J19") (pin "5") (pintype "passive"))
      (node (ref "J19") (pin "6") (pintype "passive"))
      (node (ref "J19") (pin "7") (pintype "passive"))
      (node (ref "J19") (pin "8") (pintype "passive"))
      (node (ref "J19") (pin "9") (pintype "passive"))
      (node (ref "J25") (pin "21") (pintype "passive"))
      (node (ref "J25") (pin "7") (pintype "passive"))
      (node (ref "J41") (pin "5") (pintype "passive"))
      (node (ref "J41") (pin "6") (pintype "passive"))
      (node (ref "J41") (pin "7") (pintype "passive"))
      (node (ref "J41") (pin "8") (pintype "passive"))
      (node (ref "J41") (pin "9") (pintype "passive"))
    )
    (net (code "58") (name "/C20+") (class "Default")
      (node (ref "J24") (pin "1") (pintype "passive"))
      (node (ref "J24") (pin "2") (pintype "passive"))
      (node (ref "J45") (pin "1") (pintype "passive"))
      (node (ref "J45") (pin "2") (pintype "passive"))
      (node (ref "P39") (pin "1") (pinfunction "1_1") (pintype "passive"))
    )
    (net (code "59") (name "/C20-") (class "Default")
      (node (ref "J24") (pin "3") (pintype "passive"))
      (node (ref "J24") (pin "4") (pintype "passive"))
      (node (ref "J45") (pin "3") (pintype "passive"))
      (node (ref "J45") (pin "4") (pintype "passive"))
      (node (ref "P39") (pin "2") (pinfunction "2_2") (pintype "passive"))
    )
    (net (code "60") (name "/C20SH") (class "Default")
      (node (ref "J24") (pin "5") (pintype "passive"))
      (node (ref "J24") (pin "6") (pintype "passive"))
      (node (ref "J24") (pin "7") (pintype "passive"))
      (node (ref "J24") (pin "8") (pintype "passive"))
      (node (ref "J24") (pin "9") (pintype "passive"))
      (node (ref "J25") (pin "10") (pintype "passive"))
      (node (ref "J25") (pin "24") (pintype "passive"))
      (node (ref "J45") (pin "5") (pintype "passive"))
      (node (ref "J45") (pin "6") (pintype "passive"))
      (node (ref "J45") (pin "7") (pintype "passive"))
      (node (ref "J45") (pin "8") (pintype "passive"))
      (node (ref "J45") (pin "9") (pintype "passive"))
    )
    (net (code "61") (name "/S1+") (class "Default")
      (node (ref "J1") (pin "14") (pintype "passive"))
      (node (ref "J1") (pin "2") (pintype "passive"))
      (node (ref "P2") (pin "1") (pinfunction "1_1") (pintype "passive"))
    )
    (net (code "62") (name "/S1-") (class "Default")
      (node (ref "J1") (pin "16") (pintype "passive"))
      (node (ref "J1") (pin "3") (pintype "passive"))
      (node (ref "P2") (pin "2") (pinfunction "2_2") (pintype "passive"))
    )
    (net (code "63") (name "/S2+") (class "Default")
      (node (ref "J1") (pin "17") (pintype "passive"))
      (node (ref "J1") (pin "5") (pintype "passive"))
      (node (ref "P10") (pin "1") (pinfunction "1_1") (pintype "passive"))
    )
    (net (code "64") (name "/S2-") (class "Default")
      (node (ref "J1") (pin "19") (pintype "passive"))
      (node (ref "J1") (pin "6") (pintype "passive"))
      (node (ref "P10") (pin "2") (pinfunction "2_2") (pintype "passive"))
    )
    (net (code "65") (name "/S3+") (class "Default")
      (node (ref "J1") (pin "20") (pintype "passive"))
      (node (ref "J1") (pin "8") (pintype "passive"))
      (node (ref "P18") (pin "1") (pinfunction "1_1") (pintype "passive"))
    )
    (net (code "66") (name "/S3-") (class "Default")
      (node (ref "J1") (pin "22") (pintype "passive"))
      (node (ref "J1") (pin "9") (pintype "passive"))
      (node (ref "P18") (pin "2") (pinfunction "2_2") (pintype "passive"))
    )
    (net (code "67") (name "/S4+") (class "Default")
      (node (ref "J1") (pin "11") (pintype "passive"))
      (node (ref "J1") (pin "23") (pintype "passive"))
      (node (ref "P26") (pin "1") (pinfunction "1_1") (pintype "passive"))
    )
    (net (code "68") (name "/S4-") (class "Default")
      (node (ref "J1") (pin "12") (pintype "passive"))
      (node (ref "J1") (pin "25") (pintype "passive"))
      (node (ref "P26") (pin "2") (pinfunction "2_2") (pintype "passive"))
    )
    (net (code "69") (name "/S5+") (class "Default")
      (node (ref "J10") (pin "14") (pintype "passive"))
      (node (ref "J10") (pin "2") (pintype "passive"))
      (node (ref "P34") (pin "1") (pinfunction "1_1") (pintype "passive"))
    )
    (net (code "70") (name "/S5-") (class "Default")
      (node (ref "J10") (pin "16") (pintype "passive"))
      (node (ref "J10") (pin "3") (pintype "passive"))
      (node (ref "P34") (pin "2") (pinfunction "2_2") (pintype "passive"))
    )
    (net (code "71") (name "/S6+") (class "Default")
      (node (ref "J10") (pin "17") (pintype "passive"))
      (node (ref "J10") (pin "5") (pintype "passive"))
      (node (ref "P4") (pin "1") (pinfunction "1_1") (pintype "passive"))
    )
    (net (code "72") (name "/S6-") (class "Default")
      (node (ref "J10") (pin "19") (pintype "passive"))
      (node (ref "J10") (pin "6") (pintype "passive"))
      (node (ref "P4") (pin "2") (pinfunction "2_2") (pintype "passive"))
    )
    (net (code "73") (name "/S7+") (class "Default")
      (node (ref "J10") (pin "20") (pintype "passive"))
      (node (ref "J10") (pin "8") (pintype "passive"))
      (node (ref "P12") (pin "1") (pinfunction "1_1") (pintype "passive"))
    )
    (net (code "74") (name "/S7-") (class "Default")
      (node (ref "J10") (pin "22") (pintype "passive"))
      (node (ref "J10") (pin "9") (pintype "passive"))
      (node (ref "P12") (pin "2") (pinfunction "2_2") (pintype "passive"))
    )
    (net (code "75") (name "/S8+") (class "Default")
      (node (ref "J10") (pin "11") (pintype "passive"))
      (node (ref "J10") (pin "23") (pintype "passive"))
      (node (ref "P20") (pin "1") (pinfunction "1_1") (pintype "passive"))
    )
    (net (code "76") (name "/S8-") (class "Default")
      (node (ref "J10") (pin "12") (pintype "passive"))
      (node (ref "J10") (pin "25") (pintype "passive"))
      (node (ref "P20") (pin "2") (pinfunction "2_2") (pintype "passive"))
    )
    (net (code "77") (name "/S9+") (class "Default")
      (node (ref "J15") (pin "14") (pintype "passive"))
      (node (ref "J15") (pin "2") (pintype "passive"))
      (node (ref "P28") (pin "1") (pinfunction "1_1") (pintype "passive"))
    )
    (net (code "78") (name "/S9-") (class "Default")
      (node (ref "J15") (pin "16") (pintype "passive"))
      (node (ref "J15") (pin "3") (pintype "passive"))
      (node (ref "P28") (pin "2") (pinfunction "2_2") (pintype "passive"))
    )
    (net (code "79") (name "/S10+") (class "Default")
      (node (ref "J15") (pin "17") (pintype "passive"))
      (node (ref "J15") (pin "5") (pintype "passive"))
      (node (ref "P36") (pin "1") (pinfunction "1_1") (pintype "passive"))
    )
    (net (code "80") (name "/S10-") (class "Default")
      (node (ref "J15") (pin "19") (pintype "passive"))
      (node (ref "J15") (pin "6") (pintype "passive"))
      (node (ref "P36") (pin "2") (pinfunction "2_2") (pintype "passive"))
    )
    (net (code "81") (name "/S11+") (class "Default")
      (node (ref "J15") (pin "20") (pintype "passive"))
      (node (ref "J15") (pin "8") (pintype "passive"))
      (node (ref "P6") (pin "1") (pinfunction "1_1") (pintype "passive"))
    )
    (net (code "82") (name "/S11-") (class "Default")
      (node (ref "J15") (pin "22") (pintype "passive"))
      (node (ref "J15") (pin "9") (pintype "passive"))
      (node (ref "P6") (pin "2") (pinfunction "2_2") (pintype "passive"))
    )
    (net (code "83") (name "/S12+") (class "Default")
      (node (ref "J15") (pin "11") (pintype "passive"))
      (node (ref "J15") (pin "23") (pintype "passive"))
      (node (ref "P14") (pin "1") (pinfunction "1_1") (pintype "passive"))
    )
    (net (code "84") (name "/S12-") (class "Default")
      (node (ref "J15") (pin "12") (pintype "passive"))
      (node (ref "J15") (pin "25") (pintype "passive"))
      (node (ref "P14") (pin "2") (pinfunction "2_2") (pintype "passive"))
    )
    (net (code "85") (name "/S13+") (class "Default")
      (node (ref "J20") (pin "14") (pintype "passive"))
      (node (ref "J20") (pin "2") (pintype "passive"))
      (node (ref "P22") (pin "1") (pinfunction "1_1") (pintype "passive"))
    )
    (net (code "86") (name "/S13-") (class "Default")
      (node (ref "J20") (pin "16") (pintype "passive"))
      (node (ref "J20") (pin "3") (pintype "passive"))
      (node (ref "P22") (pin "2") (pinfunction "2_2") (pintype "passive"))
    )
    (net (code "87") (name "/S14+") (class "Default")
      (node (ref "J20") (pin "17") (pintype "passive"))
      (node (ref "J20") (pin "5") (pintype "passive"))
      (node (ref "P30") (pin "1") (pinfunction "1_1") (pintype "passive"))
    )
    (net (code "88") (name "/S14-") (class "Default")
      (node (ref "J20") (pin "19") (pintype "passive"))
      (node (ref "J20") (pin "6") (pintype "passive"))
      (node (ref "P30") (pin "2") (pinfunction "2_2") (pintype "passive"))
    )
    (net (code "89") (name "/S15+") (class "Default")
      (node (ref "J20") (pin "20") (pintype "passive"))
      (node (ref "J20") (pin "8") (pintype "passive"))
      (node (ref "P38") (pin "1") (pinfunction "1_1") (pintype "passive"))
    )
    (net (code "90") (name "/S15-") (class "Default")
      (node (ref "J20") (pin "22") (pintype "passive"))
      (node (ref "J20") (pin "9") (pintype "passive"))
      (node (ref "P38") (pin "2") (pinfunction "2_2") (pintype "passive"))
    )
    (net (code "91") (name "/S16+") (class "Default")
      (node (ref "J20") (pin "11") (pintype "passive"))
      (node (ref "J20") (pin "23") (pintype "passive"))
      (node (ref "P8") (pin "1") (pinfunction "1_1") (pintype "passive"))
    )
    (net (code "92") (name "/S16-") (class "Default")
      (node (ref "J20") (pin "12") (pintype "passive"))
      (node (ref "J20") (pin "25") (pintype "passive"))
      (node (ref "P8") (pin "2") (pinfunction "2_2") (pintype "passive"))
    )
    (net (code "93") (name "/S17+") (class "Default")
      (node (ref "J25") (pin "14") (pintype "passive"))
      (node (ref "J25") (pin "2") (pintype "passive"))
      (node (ref "P16") (pin "1") (pinfunction "1_1") (pintype "passive"))
    )
    (net (code "94") (name "/S17-") (class "Default")
      (node (ref "J25") (pin "16") (pintype "passive"))
      (node (ref "J25") (pin "3") (pintype "passive"))
      (node (ref "P16") (pin "2") (pinfunction "2_2") (pintype "passive"))
    )
    (net (code "95") (name "/S18+") (class "Default")
      (node (ref "J25") (pin "17") (pintype "passive"))
      (node (ref "J25") (pin "5") (pintype "passive"))
      (node (ref "J25") (pin "6") (pintype "passive"))
      (node (ref "P24") (pin "1") (pinfunction "1_1") (pintype "passive"))
    )
    (net (code "96") (name "/S18-") (class "Default")
      (node (ref "J25") (pin "19") (pintype "passive"))
      (node (ref "P24") (pin "2") (pinfunction "2_2") (pintype "passive"))
    )
    (net (code "97") (name "/S19+") (class "Default")
      (node (ref "J25") (pin "20") (pintype "passive"))
      (node (ref "J25") (pin "8") (pintype "passive"))
      (node (ref "P32") (pin "1") (pinfunction "1_1") (pintype "passive"))
    )
    (net (code "98") (name "/S19-") (class "Default")
      (node (ref "J25") (pin "22") (pintype "passive"))
      (node (ref "J25") (pin "9") (pintype "passive"))
      (node (ref "P32") (pin "2") (pinfunction "2_2") (pintype "passive"))
    )
    (net (code "99") (name "/S20+") (class "Default")
      (node (ref "J25") (pin "11") (pintype "passive"))
      (node (ref "J25") (pin "23") (pintype "passive"))
      (node (ref "P40") (pin "1") (pinfunction "1_1") (pintype "passive"))
    )
    (net (code "100") (name "/S20-") (class "Default")
      (node (ref "J25") (pin "12") (pintype "passive"))
      (node (ref "J25") (pin "25") (pintype "passive"))
      (node (ref "P40") (pin "2") (pinfunction "2_2") (pintype "passive"))
    )
    (net (code "101") (name "unconnected-(J1-Pad13)") (class "Default")
      (node (ref "J1") (pin "13") (pintype "passive"))
    )
    (net (code "102") (name "unconnected-(J10-Pad13)") (class "Default")
      (node (ref "J10") (pin "13") (pintype "passive"))
    )
    (net (code "103") (name "unconnected-(J15-Pad13)") (class "Default")
      (node (ref "J15") (pin "13") (pintype "passive"))
    )
    (net (code "104") (name "unconnected-(J20-Pad13)") (class "Default")
      (node (ref "J20") (pin "13") (pintype "passive"))
    )
    (net (code "105") (name "unconnected-(J25-Pad13)") (class "Default")
      (node (ref "J25") (pin "13") (pintype "passive"))
    )
  )
)
